# ford_giraffe.net
KiCad netlist of a schematic drawn in EAGLE
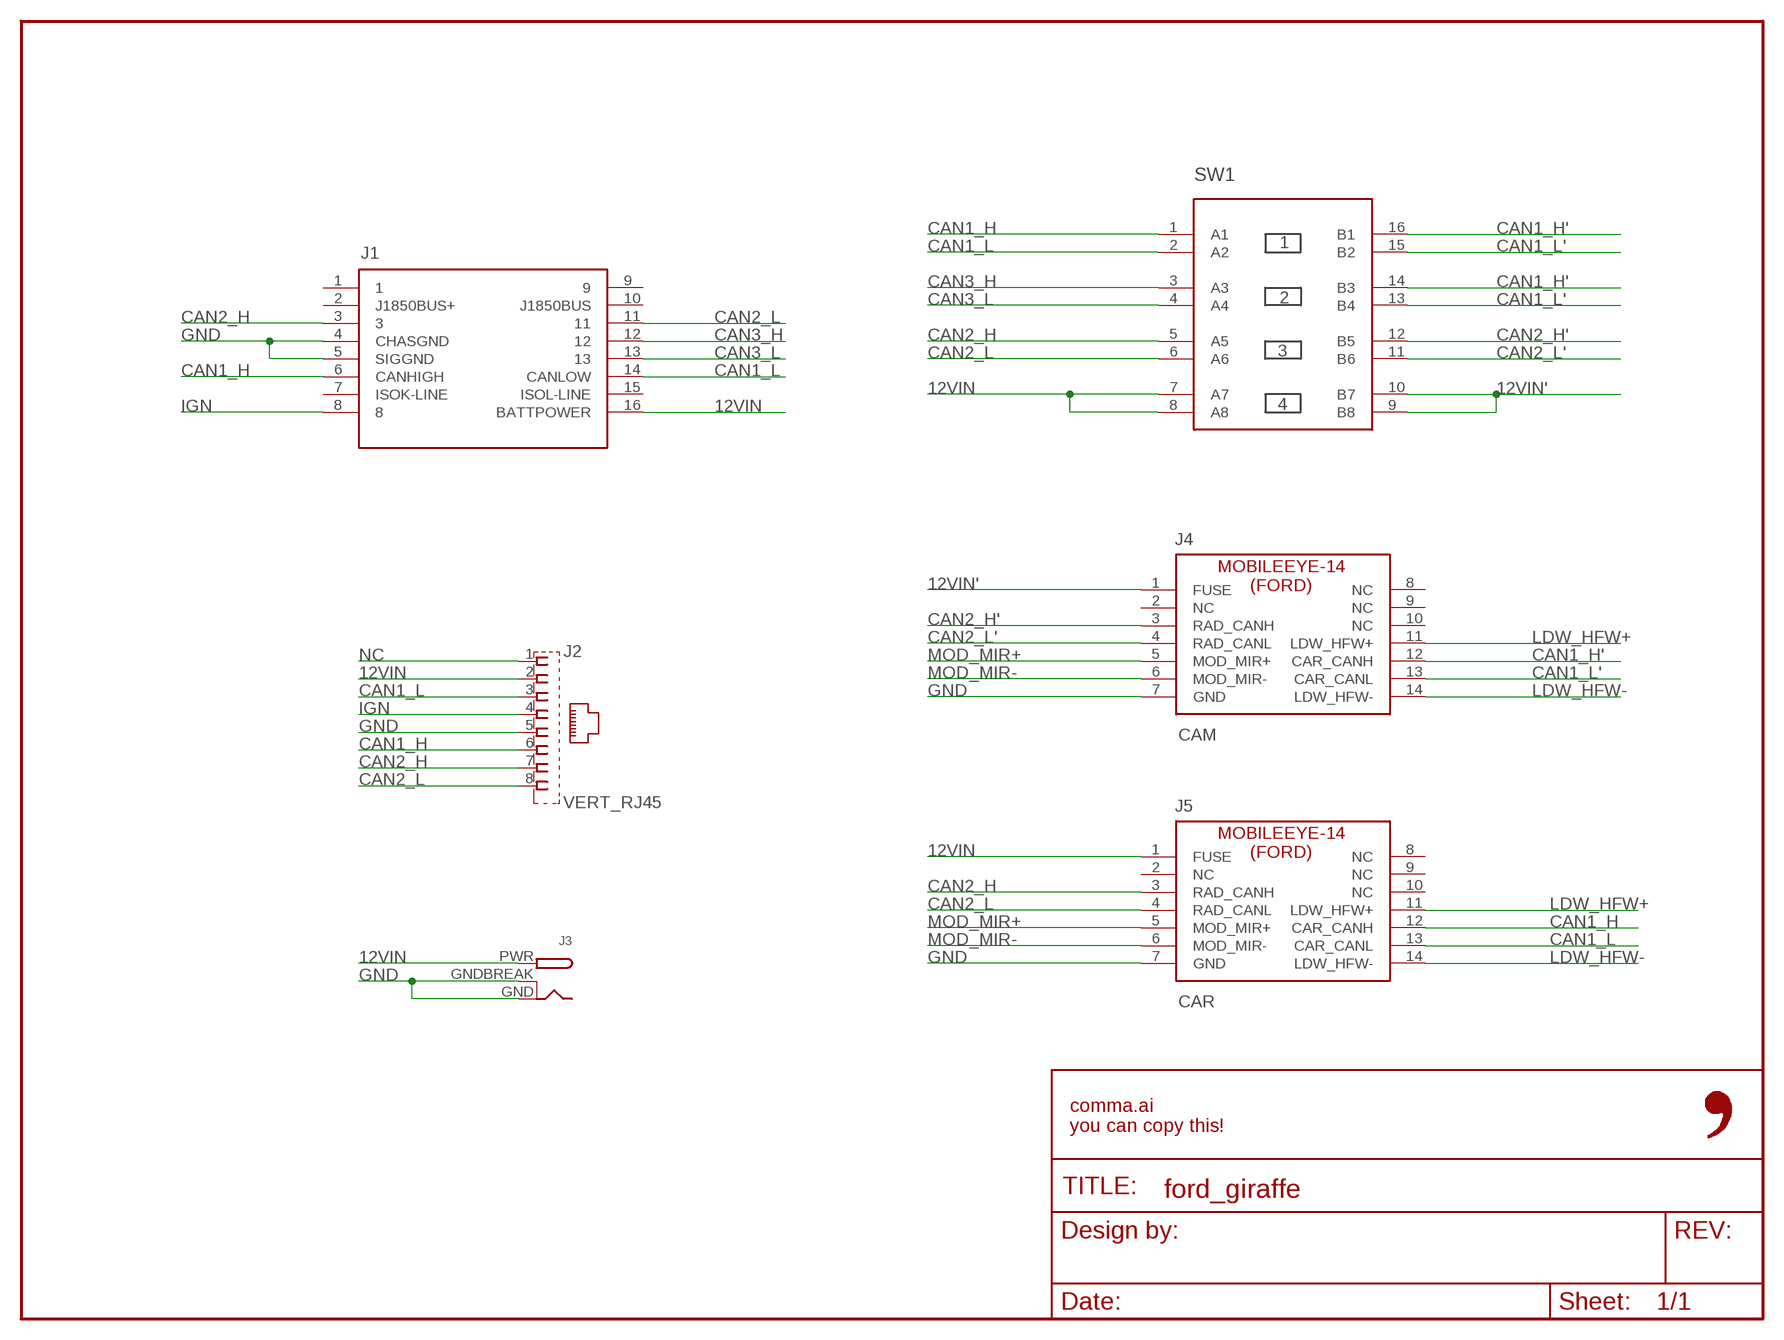
[diagram p0: schematic, sheet 1]

(export (version "E")
  (design (tool "Eeschema 10.0.6"))
  (components
    (comp (ref "FRAME1")
      (value "FRAME-LETTER-OPENNO_PACKAGE")
      (footprint "eagle-import:DUMMY")
      (fields (field (name "DESIGNER") "Nobody"))
      (libsource (lib "eagle-import") (part "FRAME-LETTER-OPENNO_PACKAGE"))
    )
    (comp (ref "J1")
      (value "OBDII-FEMALE-CUT")
      (footprint "eagle-import:OBDII-FEMALE-MIDCUT")
      (libsource (lib "eagle-import") (part "OBDII-FEMALE-CUT"))
    )
    (comp (ref "J2")
      (value "VERT_RJ45")
      (footprint "eagle-import:GLX-S-88M")
      (libsource (lib "eagle-import") (part "VERT_RJ45"))
    )
    (comp (ref "J3")
      (value "DCBARRELPTH")
      (footprint "eagle-import:DCJACK_2MM_PTH")
      (libsource (lib "eagle-import") (part "DCBARRELPTH"))
    )
    (comp (ref "J4")
      (value "CAM")
      (footprint "eagle-import:2X7-FORD-CAR")
      (libsource (lib "eagle-import") (part "MOBILEEYE-14-F"))
    )
    (comp (ref "J5")
      (value "CAR")
      (footprint "eagle-import:2X7-FORD-CAM")
      (libsource (lib "eagle-import") (part "MOBILEEYE-14-M"))
    )
    (comp (ref "SW1")
      (value "4XDPSTSMT")
      (footprint "eagle-import:4-DPST")
      (libsource (lib "eagle-import") (part "4XDPSTSMT"))
    )
  )
  (nets
    (net (code "1") (name "/12VIN") (class "Default")
      (node (ref "J1") (pin "16") (pinfunction "BATTPOWER_16") (pintype "bidirectional"))
      (node (ref "J2") (pin "2") (pinfunction "2_2") (pintype "passive"))
      (node (ref "J3") (pin "PWR") (pinfunction "PWR_PWR") (pintype "power_in"))
      (node (ref "J5") (pin "1") (pinfunction "FUSE_1") (pintype "bidirectional"))
      (node (ref "SW1") (pin "7") (pinfunction "A7_7") (pintype "bidirectional"))
      (node (ref "SW1") (pin "8") (pinfunction "A8_8") (pintype "bidirectional"))
    )
    (net (code "2") (name "/12VIN'") (class "Default")
      (node (ref "J4") (pin "1") (pinfunction "FUSE_1") (pintype "bidirectional"))
      (node (ref "SW1") (pin "10") (pinfunction "B7_10") (pintype "bidirectional"))
      (node (ref "SW1") (pin "9") (pinfunction "B8_9") (pintype "bidirectional"))
    )
    (net (code "3") (name "/CAN1_H") (class "Default")
      (node (ref "J1") (pin "6") (pinfunction "CANHIGH_6") (pintype "bidirectional"))
      (node (ref "J2") (pin "6") (pinfunction "6_6") (pintype "passive"))
      (node (ref "J5") (pin "12") (pinfunction "CAR_CANH_12") (pintype "bidirectional"))
      (node (ref "SW1") (pin "1") (pinfunction "A1_1") (pintype "bidirectional"))
    )
    (net (code "4") (name "/CAN1_H'") (class "Default")
      (node (ref "J4") (pin "12") (pinfunction "CAR_CANH_12") (pintype "bidirectional"))
      (node (ref "SW1") (pin "14") (pinfunction "B3_14") (pintype "bidirectional"))
      (node (ref "SW1") (pin "16") (pinfunction "B1_16") (pintype "bidirectional"))
    )
    (net (code "5") (name "/CAN1_L") (class "Default")
      (node (ref "J1") (pin "14") (pinfunction "CANLOW_14") (pintype "bidirectional"))
      (node (ref "J2") (pin "3") (pinfunction "3_3") (pintype "passive"))
      (node (ref "J5") (pin "13") (pinfunction "CAR_CANL_13") (pintype "bidirectional"))
      (node (ref "SW1") (pin "2") (pinfunction "A2_2") (pintype "bidirectional"))
    )
    (net (code "6") (name "/CAN1_L'") (class "Default")
      (node (ref "J4") (pin "13") (pinfunction "CAR_CANL_13") (pintype "bidirectional"))
      (node (ref "SW1") (pin "13") (pinfunction "B4_13") (pintype "bidirectional"))
      (node (ref "SW1") (pin "15") (pinfunction "B2_15") (pintype "bidirectional"))
    )
    (net (code "7") (name "/CAN2_H") (class "Default")
      (node (ref "J1") (pin "3") (pinfunction "3_3") (pintype "bidirectional"))
      (node (ref "J2") (pin "7") (pinfunction "7_7") (pintype "passive"))
      (node (ref "J5") (pin "3") (pinfunction "RAD_CANH_3") (pintype "bidirectional"))
      (node (ref "SW1") (pin "5") (pinfunction "A5_5") (pintype "bidirectional"))
    )
    (net (code "8") (name "/CAN2_H'") (class "Default")
      (node (ref "J4") (pin "3") (pinfunction "RAD_CANH_3") (pintype "bidirectional"))
      (node (ref "SW1") (pin "12") (pinfunction "B5_12") (pintype "bidirectional"))
    )
    (net (code "9") (name "/CAN2_L") (class "Default")
      (node (ref "J1") (pin "11") (pinfunction "11_11") (pintype "bidirectional"))
      (node (ref "J2") (pin "8") (pinfunction "8_8") (pintype "passive"))
      (node (ref "J5") (pin "4") (pinfunction "RAD_CANL_4") (pintype "bidirectional"))
      (node (ref "SW1") (pin "6") (pinfunction "A6_6") (pintype "bidirectional"))
    )
    (net (code "10") (name "/CAN2_L'") (class "Default")
      (node (ref "J4") (pin "4") (pinfunction "RAD_CANL_4") (pintype "bidirectional"))
      (node (ref "SW1") (pin "11") (pinfunction "B6_11") (pintype "bidirectional"))
    )
    (net (code "11") (name "/CAN3_H") (class "Default")
      (node (ref "J1") (pin "12") (pinfunction "12_12") (pintype "bidirectional"))
      (node (ref "SW1") (pin "3") (pinfunction "A3_3") (pintype "bidirectional"))
    )
    (net (code "12") (name "/CAN3_L") (class "Default")
      (node (ref "J1") (pin "13") (pinfunction "13_13") (pintype "bidirectional"))
      (node (ref "SW1") (pin "4") (pinfunction "A4_4") (pintype "bidirectional"))
    )
    (net (code "13") (name "/GND") (class "Default")
      (node (ref "J1") (pin "4") (pinfunction "CHASGND_4") (pintype "bidirectional"))
      (node (ref "J1") (pin "5") (pinfunction "SIGGND_5") (pintype "bidirectional"))
      (node (ref "J2") (pin "5") (pinfunction "5_5") (pintype "passive"))
      (node (ref "J3") (pin "GND") (pinfunction "GND_GND") (pintype "power_in"))
      (node (ref "J3") (pin "GNDBREAK") (pinfunction "GNDBREAK_GNDBREAK") (pintype "power_in"))
      (node (ref "J4") (pin "7") (pinfunction "GND_7") (pintype "bidirectional"))
      (node (ref "J5") (pin "7") (pinfunction "GND_7") (pintype "bidirectional"))
    )
    (net (code "14") (name "/IGN") (class "Default")
      (node (ref "J1") (pin "8") (pinfunction "8_8") (pintype "bidirectional"))
      (node (ref "J2") (pin "4") (pinfunction "4_4") (pintype "passive"))
    )
    (net (code "15") (name "/LDW_HFW+") (class "Default")
      (node (ref "J4") (pin "11") (pinfunction "LDW_HFW+_11") (pintype "bidirectional"))
      (node (ref "J5") (pin "11") (pinfunction "LDW_HFW+_11") (pintype "bidirectional"))
    )
    (net (code "16") (name "/LDW_HFW-") (class "Default")
      (node (ref "J4") (pin "14") (pinfunction "LDW_HFW-_14") (pintype "bidirectional"))
      (node (ref "J5") (pin "14") (pinfunction "LDW_HFW-_14") (pintype "bidirectional"))
    )
    (net (code "17") (name "/MOD_MIR+") (class "Default")
      (node (ref "J4") (pin "5") (pinfunction "MOD_MIR+_5") (pintype "bidirectional"))
      (node (ref "J5") (pin "5") (pinfunction "MOD_MIR+_5") (pintype "bidirectional"))
    )
    (net (code "18") (name "/MOD_MIR-") (class "Default")
      (node (ref "J4") (pin "6") (pinfunction "MOD_MIR-_6") (pintype "bidirectional"))
      (node (ref "J5") (pin "6") (pinfunction "MOD_MIR-_6") (pintype "bidirectional"))
    )
    (net (code "19") (name "/NC") (class "Default")
      (node (ref "J2") (pin "1") (pinfunction "1_1") (pintype "passive"))
    )
    (net (code "20") (name "unconnected-(J1-ISOK-LINE-Pad7)") (class "Default")
      (node (ref "J1") (pin "7") (pinfunction "ISOK-LINE_7") (pintype "bidirectional"))
    )
    (net (code "21") (name "unconnected-(J1-ISOL-LINE-Pad15)") (class "Default")
      (node (ref "J1") (pin "15") (pinfunction "ISOL-LINE_15") (pintype "bidirectional"))
    )
    (net (code "22") (name "unconnected-(J1-J1850BUS+-Pad2)") (class "Default")
      (node (ref "J1") (pin "2") (pinfunction "J1850BUS+_2") (pintype "bidirectional"))
    )
    (net (code "23") (name "unconnected-(J1-J1850BUS-Pad10)") (class "Default")
      (node (ref "J1") (pin "10") (pinfunction "J1850BUS_10") (pintype "bidirectional"))
    )
    (net (code "24") (name "unconnected-(J1-Pad1)") (class "Default")
      (node (ref "J1") (pin "1") (pinfunction "1_1") (pintype "bidirectional"))
    )
    (net (code "25") (name "unconnected-(J1-Pad9)") (class "Default")
      (node (ref "J1") (pin "9") (pinfunction "9_9") (pintype "bidirectional"))
    )
    (net (code "26") (name "unconnected-(J4-NC-Pad2)") (class "Default")
      (node (ref "J4") (pin "2") (pinfunction "NC_2") (pintype "bidirectional"))
    )
    (net (code "27") (name "unconnected-(J4-NC-Pad8)") (class "Default")
      (node (ref "J4") (pin "8") (pinfunction "NC_8") (pintype "bidirectional"))
    )
    (net (code "28") (name "unconnected-(J4-NC-Pad9)") (class "Default")
      (node (ref "J4") (pin "9") (pinfunction "NC_9") (pintype "bidirectional"))
    )
    (net (code "29") (name "unconnected-(J4-NC-Pad10)") (class "Default")
      (node (ref "J4") (pin "10") (pinfunction "NC_10") (pintype "bidirectional"))
    )
    (net (code "30") (name "unconnected-(J5-NC-Pad2)") (class "Default")
      (node (ref "J5") (pin "2") (pinfunction "NC_2") (pintype "bidirectional"))
    )
    (net (code "31") (name "unconnected-(J5-NC-Pad8)") (class "Default")
      (node (ref "J5") (pin "8") (pinfunction "NC_8") (pintype "bidirectional"))
    )
    (net (code "32") (name "unconnected-(J5-NC-Pad9)") (class "Default")
      (node (ref "J5") (pin "9") (pinfunction "NC_9") (pintype "bidirectional"))
    )
    (net (code "33") (name "unconnected-(J5-NC-Pad10)") (class "Default")
      (node (ref "J5") (pin "10") (pinfunction "NC_10") (pintype "bidirectional"))
    )
  )
)
